# PWM_LED.net
KiCad netlist of a schematic drawn in Altium Designer
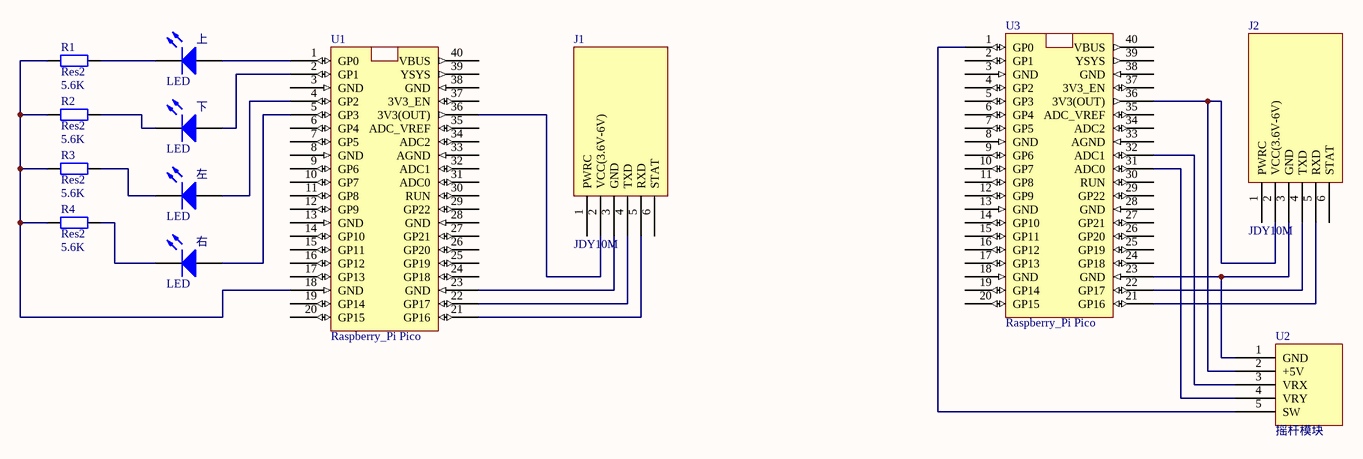
[diagram p0: PWM控制LED.SchDoc]

(export (version "E")
  (design (tool "Eeschema 10.0.6"))
  (components
    (comp (ref "J1") (value "JDY10M") (libsource (lib "元器件") (part "JDY10M")))
    (comp (ref "J2") (value "JDY10M") (libsource (lib "元器件") (part "JDY10M")))
    (comp (ref "R1")
      (value "Res2")
      (footprint "AXIAL-0.4")
      (description "Resistor")
      (fields (field (name "ALTIUM_VALUE") "5.6K") (field (name "PUBLISHER") "Altium Limited"))
      (libsource (lib "Miscellaneous Devices") (part "Res2"))
    )
    (comp (ref "R2")
      (value "Res2")
      (footprint "AXIAL-0.4")
      (description "Resistor")
      (fields (field (name "ALTIUM_VALUE") "5.6K") (field (name "PUBLISHER") "Altium Limited"))
      (libsource (lib "Miscellaneous Devices") (part "Res2"))
    )
    (comp (ref "R3")
      (value "Res2")
      (footprint "AXIAL-0.4")
      (description "Resistor")
      (fields (field (name "ALTIUM_VALUE") "5.6K") (field (name "PUBLISHER") "Altium Limited"))
      (libsource (lib "Miscellaneous Devices") (part "Res2"))
    )
    (comp (ref "R4")
      (value "Res2")
      (footprint "AXIAL-0.4")
      (description "Resistor")
      (fields (field (name "ALTIUM_VALUE") "5.6K") (field (name "PUBLISHER") "Altium Limited"))
      (libsource (lib "Miscellaneous Devices") (part "Res2"))
    )
    (comp (ref "U1") (value "Raspberry_Pi Pico") (libsource (lib "元器件") (part "Raspberry_Pi Pico")))
    (comp (ref "U2") (value "摇杆模块") (libsource (lib "元器件") (part "摇杆模块")))
    (comp (ref "U3") (value "Raspberry_Pi Pico") (libsource (lib "元器件") (part "Raspberry_Pi Pico")))
    (comp (ref "上")
      (value "LED")
      (footprint "LED-0")
      (description "Typical INFRARED GaAs LED")
      (fields (field (name "PUBLISHER") "Altium Limited"))
      (libsource (lib "Miscellaneous Devices") (part "LED0"))
    )
    (comp (ref "下")
      (value "LED")
      (footprint "LED-0")
      (description "Typical INFRARED GaAs LED")
      (fields (field (name "PUBLISHER") "Altium Limited"))
      (libsource (lib "Miscellaneous Devices") (part "LED0"))
    )
    (comp (ref "右")
      (value "LED")
      (footprint "LED-0")
      (description "Typical INFRARED GaAs LED")
      (fields (field (name "PUBLISHER") "Altium Limited"))
      (libsource (lib "Miscellaneous Devices") (part "LED0"))
    )
    (comp (ref "左")
      (value "LED")
      (footprint "LED-0")
      (description "Typical INFRARED GaAs LED")
      (fields (field (name "PUBLISHER") "Altium Limited"))
      (libsource (lib "Miscellaneous Devices") (part "LED0"))
    )
  )
  (nets
    (net (code "1") (name "Net-(J1-GND)") (class "Default")
      (node (ref "J1") (pin "3") (pinfunction "GND_3") (pintype "passive"))
      (node (ref "U1") (pin "23") (pinfunction "GND_23") (pintype "input"))
    )
    (net (code "2") (name "Net-(J1-RXD)") (class "Default")
      (node (ref "J1") (pin "5") (pinfunction "RXD_5") (pintype "passive"))
      (node (ref "U1") (pin "21") (pinfunction "GP16_21") (pintype "bidirectional"))
    )
    (net (code "3") (name "Net-(J1-TXD)") (class "Default")
      (node (ref "J1") (pin "4") (pinfunction "TXD_4") (pintype "passive"))
      (node (ref "U1") (pin "22") (pinfunction "GP17_22") (pintype "bidirectional"))
    )
    (net (code "4") (name "Net-(J1-VCC(3.6V-6V))") (class "Default")
      (node (ref "J1") (pin "2") (pinfunction "VCC(3.6V-6V)_2") (pintype "passive"))
      (node (ref "U1") (pin "36") (pinfunction "3V3(OUT)_36") (pintype "output"))
    )
    (net (code "5") (name "Net-(J2-GND)") (class "Default")
      (node (ref "J2") (pin "3") (pinfunction "GND_3") (pintype "passive"))
      (node (ref "U2") (pin "1") (pinfunction "GND_1") (pintype "passive"))
      (node (ref "U3") (pin "23") (pinfunction "GND_23") (pintype "input"))
    )
    (net (code "6") (name "Net-(J2-RXD)") (class "Default")
      (node (ref "J2") (pin "5") (pinfunction "RXD_5") (pintype "passive"))
      (node (ref "U3") (pin "21") (pinfunction "GP16_21") (pintype "bidirectional"))
    )
    (net (code "7") (name "Net-(J2-TXD)") (class "Default")
      (node (ref "J2") (pin "4") (pinfunction "TXD_4") (pintype "passive"))
      (node (ref "U3") (pin "22") (pinfunction "GP17_22") (pintype "bidirectional"))
    )
    (net (code "8") (name "Net-(J2-VCC(3.6V-6V))") (class "Default")
      (node (ref "J2") (pin "2") (pinfunction "VCC(3.6V-6V)_2") (pintype "passive"))
      (node (ref "U2") (pin "2") (pinfunction "+5V_2") (pintype "passive"))
      (node (ref "U3") (pin "36") (pinfunction "3V3(OUT)_36") (pintype "output"))
    )
    (net (code "9") (name "Net-(R1-Pad1)") (class "Default")
      (node (ref "R1") (pin "1") (pinfunction "1_1") (pintype "passive"))
      (node (ref "R2") (pin "1") (pinfunction "1_1") (pintype "passive"))
      (node (ref "R3") (pin "1") (pinfunction "1_1") (pintype "passive"))
      (node (ref "R4") (pin "1") (pinfunction "1_1") (pintype "passive"))
      (node (ref "U1") (pin "18") (pinfunction "GND_18") (pintype "input"))
    )
    (net (code "10") (name "Net-(U1-GP0)") (class "Default")
      (node (ref "U1") (pin "1") (pinfunction "GP0_1") (pintype "bidirectional"))
      (node (ref "上") (pin "1") (pinfunction "A_1") (pintype "passive"))
    )
    (net (code "11") (name "Net-(U1-GP1)") (class "Default")
      (node (ref "U1") (pin "2") (pinfunction "GP1_2") (pintype "bidirectional"))
      (node (ref "下") (pin "1") (pinfunction "A_1") (pintype "passive"))
    )
    (net (code "12") (name "Net-(U1-GP2)") (class "Default")
      (node (ref "U1") (pin "4") (pinfunction "GP2_4") (pintype "bidirectional"))
      (node (ref "左") (pin "1") (pinfunction "A_1") (pintype "passive"))
    )
    (net (code "13") (name "Net-(U1-GP3)") (class "Default")
      (node (ref "U1") (pin "5") (pinfunction "GP3_5") (pintype "bidirectional"))
      (node (ref "右") (pin "1") (pinfunction "A_1") (pintype "passive"))
    )
    (net (code "14") (name "Net-(U2-SW)") (class "Default")
      (node (ref "U2") (pin "5") (pinfunction "SW_5") (pintype "passive"))
      (node (ref "U3") (pin "1") (pinfunction "GP0_1") (pintype "bidirectional"))
    )
    (net (code "15") (name "Net-(U2-VRX)") (class "Default")
      (node (ref "U2") (pin "3") (pinfunction "VRX_3") (pintype "passive"))
      (node (ref "U3") (pin "32") (pinfunction "ADC1_32") (pintype "bidirectional"))
    )
    (net (code "16") (name "Net-(U2-VRY)") (class "Default")
      (node (ref "U2") (pin "4") (pinfunction "VRY_4") (pintype "passive"))
      (node (ref "U3") (pin "31") (pinfunction "ADC0_31") (pintype "bidirectional"))
    )
    (net (code "17") (name "Net-(上-K)") (class "Default")
      (node (ref "R1") (pin "2") (pinfunction "2_2") (pintype "passive"))
      (node (ref "上") (pin "2") (pinfunction "K_2") (pintype "passive"))
    )
    (net (code "18") (name "Net-(下-K)") (class "Default")
      (node (ref "R2") (pin "2") (pinfunction "2_2") (pintype "passive"))
      (node (ref "下") (pin "2") (pinfunction "K_2") (pintype "passive"))
    )
    (net (code "19") (name "Net-(右-K)") (class "Default")
      (node (ref "R4") (pin "2") (pinfunction "2_2") (pintype "passive"))
      (node (ref "右") (pin "2") (pinfunction "K_2") (pintype "passive"))
    )
    (net (code "20") (name "Net-(左-K)") (class "Default")
      (node (ref "R3") (pin "2") (pinfunction "2_2") (pintype "passive"))
      (node (ref "左") (pin "2") (pinfunction "K_2") (pintype "passive"))
    )
    (net (code "21") (name "unconnected-(J1-PWRC-Pad1)") (class "Default")
      (node (ref "J1") (pin "1") (pinfunction "PWRC_1") (pintype "passive"))
    )
    (net (code "22") (name "unconnected-(J1-STAT-Pad6)") (class "Default")
      (node (ref "J1") (pin "6") (pinfunction "STAT_6") (pintype "passive"))
    )
    (net (code "23") (name "unconnected-(J2-PWRC-Pad1)") (class "Default")
      (node (ref "J2") (pin "1") (pinfunction "PWRC_1") (pintype "passive"))
    )
    (net (code "24") (name "unconnected-(J2-STAT-Pad6)") (class "Default")
      (node (ref "J2") (pin "6") (pinfunction "STAT_6") (pintype "passive"))
    )
    (net (code "25") (name "unconnected-(U1-3V3_EN-Pad37)") (class "Default")
      (node (ref "U1") (pin "37") (pinfunction "3V3_EN_37") (pintype "bidirectional"))
    )
    (net (code "26") (name "unconnected-(U1-ADC0-Pad31)") (class "Default")
      (node (ref "U1") (pin "31") (pinfunction "ADC0_31") (pintype "bidirectional"))
    )
    (net (code "27") (name "unconnected-(U1-ADC1-Pad32)") (class "Default")
      (node (ref "U1") (pin "32") (pinfunction "ADC1_32") (pintype "bidirectional"))
    )
    (net (code "28") (name "unconnected-(U1-ADC2-Pad34)") (class "Default")
      (node (ref "U1") (pin "34") (pinfunction "ADC2_34") (pintype "bidirectional"))
    )
    (net (code "29") (name "unconnected-(U1-ADC_VREF-Pad35)") (class "Default")
      (node (ref "U1") (pin "35") (pinfunction "ADC_VREF_35") (pintype "bidirectional"))
    )
    (net (code "30") (name "unconnected-(U1-AGND-Pad33)") (class "Default")
      (node (ref "U1") (pin "33") (pinfunction "AGND_33") (pintype "input"))
    )
    (net (code "31") (name "unconnected-(U1-GND-Pad3)") (class "Default")
      (node (ref "U1") (pin "3") (pinfunction "GND_3") (pintype "input"))
    )
    (net (code "32") (name "unconnected-(U1-GND-Pad8)") (class "Default")
      (node (ref "U1") (pin "8") (pinfunction "GND_8") (pintype "input"))
    )
    (net (code "33") (name "unconnected-(U1-GND-Pad13)") (class "Default")
      (node (ref "U1") (pin "13") (pinfunction "GND_13") (pintype "input"))
    )
    (net (code "34") (name "unconnected-(U1-GND-Pad28)") (class "Default")
      (node (ref "U1") (pin "28") (pinfunction "GND_28") (pintype "input"))
    )
    (net (code "35") (name "unconnected-(U1-GND-Pad38)") (class "Default")
      (node (ref "U1") (pin "38") (pinfunction "GND_38") (pintype "input"))
    )
    (net (code "36") (name "unconnected-(U1-GP4-Pad6)") (class "Default")
      (node (ref "U1") (pin "6") (pinfunction "GP4_6") (pintype "bidirectional"))
    )
    (net (code "37") (name "unconnected-(U1-GP5-Pad7)") (class "Default")
      (node (ref "U1") (pin "7") (pinfunction "GP5_7") (pintype "bidirectional"))
    )
    (net (code "38") (name "unconnected-(U1-GP6-Pad9)") (class "Default")
      (node (ref "U1") (pin "9") (pinfunction "GP6_9") (pintype "bidirectional"))
    )
    (net (code "39") (name "unconnected-(U1-GP7-Pad10)") (class "Default")
      (node (ref "U1") (pin "10") (pinfunction "GP7_10") (pintype "bidirectional"))
    )
    (net (code "40") (name "unconnected-(U1-GP8-Pad11)") (class "Default")
      (node (ref "U1") (pin "11") (pinfunction "GP8_11") (pintype "bidirectional"))
    )
    (net (code "41") (name "unconnected-(U1-GP9-Pad12)") (class "Default")
      (node (ref "U1") (pin "12") (pinfunction "GP9_12") (pintype "bidirectional"))
    )
    (net (code "42") (name "unconnected-(U1-GP10-Pad14)") (class "Default")
      (node (ref "U1") (pin "14") (pinfunction "GP10_14") (pintype "bidirectional"))
    )
    (net (code "43") (name "unconnected-(U1-GP11-Pad15)") (class "Default")
      (node (ref "U1") (pin "15") (pinfunction "GP11_15") (pintype "bidirectional"))
    )
    (net (code "44") (name "unconnected-(U1-GP12-Pad16)") (class "Default")
      (node (ref "U1") (pin "16") (pinfunction "GP12_16") (pintype "bidirectional"))
    )
    (net (code "45") (name "unconnected-(U1-GP13-Pad17)") (class "Default")
      (node (ref "U1") (pin "17") (pinfunction "GP13_17") (pintype "bidirectional"))
    )
    (net (code "46") (name "unconnected-(U1-GP14-Pad19)") (class "Default")
      (node (ref "U1") (pin "19") (pinfunction "GP14_19") (pintype "bidirectional"))
    )
    (net (code "47") (name "unconnected-(U1-GP15-Pad20)") (class "Default")
      (node (ref "U1") (pin "20") (pinfunction "GP15_20") (pintype "bidirectional"))
    )
    (net (code "48") (name "unconnected-(U1-GP18-Pad24)") (class "Default")
      (node (ref "U1") (pin "24") (pinfunction "GP18_24") (pintype "bidirectional"))
    )
    (net (code "49") (name "unconnected-(U1-GP19-Pad25)") (class "Default")
      (node (ref "U1") (pin "25") (pinfunction "GP19_25") (pintype "bidirectional"))
    )
    (net (code "50") (name "unconnected-(U1-GP20-Pad26)") (class "Default")
      (node (ref "U1") (pin "26") (pinfunction "GP20_26") (pintype "bidirectional"))
    )
    (net (code "51") (name "unconnected-(U1-GP21-Pad27)") (class "Default")
      (node (ref "U1") (pin "27") (pinfunction "GP21_27") (pintype "bidirectional"))
    )
    (net (code "52") (name "unconnected-(U1-GP22-Pad29)") (class "Default")
      (node (ref "U1") (pin "29") (pinfunction "GP22_29") (pintype "bidirectional"))
    )
    (net (code "53") (name "unconnected-(U1-RUN-Pad30)") (class "Default")
      (node (ref "U1") (pin "30") (pinfunction "RUN_30") (pintype "bidirectional"))
    )
    (net (code "54") (name "unconnected-(U1-VBUS-Pad40)") (class "Default")
      (node (ref "U1") (pin "40") (pinfunction "VBUS_40") (pintype "output"))
    )
    (net (code "55") (name "unconnected-(U1-YSYS-Pad39)") (class "Default")
      (node (ref "U1") (pin "39") (pinfunction "YSYS_39") (pintype "output"))
    )
    (net (code "56") (name "unconnected-(U3-3V3_EN-Pad37)") (class "Default")
      (node (ref "U3") (pin "37") (pinfunction "3V3_EN_37") (pintype "bidirectional"))
    )
    (net (code "57") (name "unconnected-(U3-ADC2-Pad34)") (class "Default")
      (node (ref "U3") (pin "34") (pinfunction "ADC2_34") (pintype "bidirectional"))
    )
    (net (code "58") (name "unconnected-(U3-ADC_VREF-Pad35)") (class "Default")
      (node (ref "U3") (pin "35") (pinfunction "ADC_VREF_35") (pintype "bidirectional"))
    )
    (net (code "59") (name "unconnected-(U3-AGND-Pad33)") (class "Default")
      (node (ref "U3") (pin "33") (pinfunction "AGND_33") (pintype "input"))
    )
    (net (code "60") (name "unconnected-(U3-GND-Pad3)") (class "Default")
      (node (ref "U3") (pin "3") (pinfunction "GND_3") (pintype "input"))
    )
    (net (code "61") (name "unconnected-(U3-GND-Pad8)") (class "Default")
      (node (ref "U3") (pin "8") (pinfunction "GND_8") (pintype "input"))
    )
    (net (code "62") (name "unconnected-(U3-GND-Pad13)") (class "Default")
      (node (ref "U3") (pin "13") (pinfunction "GND_13") (pintype "input"))
    )
    (net (code "63") (name "unconnected-(U3-GND-Pad18)") (class "Default")
      (node (ref "U3") (pin "18") (pinfunction "GND_18") (pintype "input"))
    )
    (net (code "64") (name "unconnected-(U3-GND-Pad28)") (class "Default")
      (node (ref "U3") (pin "28") (pinfunction "GND_28") (pintype "input"))
    )
    (net (code "65") (name "unconnected-(U3-GND-Pad38)") (class "Default")
      (node (ref "U3") (pin "38") (pinfunction "GND_38") (pintype "input"))
    )
    (net (code "66") (name "unconnected-(U3-GP1-Pad2)") (class "Default")
      (node (ref "U3") (pin "2") (pinfunction "GP1_2") (pintype "bidirectional"))
    )
    (net (code "67") (name "unconnected-(U3-GP2-Pad4)") (class "Default")
      (node (ref "U3") (pin "4") (pinfunction "GP2_4") (pintype "bidirectional"))
    )
    (net (code "68") (name "unconnected-(U3-GP3-Pad5)") (class "Default")
      (node (ref "U3") (pin "5") (pinfunction "GP3_5") (pintype "bidirectional"))
    )
    (net (code "69") (name "unconnected-(U3-GP4-Pad6)") (class "Default")
      (node (ref "U3") (pin "6") (pinfunction "GP4_6") (pintype "bidirectional"))
    )
    (net (code "70") (name "unconnected-(U3-GP5-Pad7)") (class "Default")
      (node (ref "U3") (pin "7") (pinfunction "GP5_7") (pintype "bidirectional"))
    )
    (net (code "71") (name "unconnected-(U3-GP6-Pad9)") (class "Default")
      (node (ref "U3") (pin "9") (pinfunction "GP6_9") (pintype "bidirectional"))
    )
    (net (code "72") (name "unconnected-(U3-GP7-Pad10)") (class "Default")
      (node (ref "U3") (pin "10") (pinfunction "GP7_10") (pintype "bidirectional"))
    )
    (net (code "73") (name "unconnected-(U3-GP8-Pad11)") (class "Default")
      (node (ref "U3") (pin "11") (pinfunction "GP8_11") (pintype "bidirectional"))
    )
    (net (code "74") (name "unconnected-(U3-GP9-Pad12)") (class "Default")
      (node (ref "U3") (pin "12") (pinfunction "GP9_12") (pintype "bidirectional"))
    )
    (net (code "75") (name "unconnected-(U3-GP10-Pad14)") (class "Default")
      (node (ref "U3") (pin "14") (pinfunction "GP10_14") (pintype "bidirectional"))
    )
    (net (code "76") (name "unconnected-(U3-GP11-Pad15)") (class "Default")
      (node (ref "U3") (pin "15") (pinfunction "GP11_15") (pintype "bidirectional"))
    )
    (net (code "77") (name "unconnected-(U3-GP12-Pad16)") (class "Default")
      (node (ref "U3") (pin "16") (pinfunction "GP12_16") (pintype "bidirectional"))
    )
    (net (code "78") (name "unconnected-(U3-GP13-Pad17)") (class "Default")
      (node (ref "U3") (pin "17") (pinfunction "GP13_17") (pintype "bidirectional"))
    )
    (net (code "79") (name "unconnected-(U3-GP14-Pad19)") (class "Default")
      (node (ref "U3") (pin "19") (pinfunction "GP14_19") (pintype "bidirectional"))
    )
    (net (code "80") (name "unconnected-(U3-GP15-Pad20)") (class "Default")
      (node (ref "U3") (pin "20") (pinfunction "GP15_20") (pintype "bidirectional"))
    )
    (net (code "81") (name "unconnected-(U3-GP18-Pad24)") (class "Default")
      (node (ref "U3") (pin "24") (pinfunction "GP18_24") (pintype "bidirectional"))
    )
    (net (code "82") (name "unconnected-(U3-GP19-Pad25)") (class "Default")
      (node (ref "U3") (pin "25") (pinfunction "GP19_25") (pintype "bidirectional"))
    )
    (net (code "83") (name "unconnected-(U3-GP20-Pad26)") (class "Default")
      (node (ref "U3") (pin "26") (pinfunction "GP20_26") (pintype "bidirectional"))
    )
    (net (code "84") (name "unconnected-(U3-GP21-Pad27)") (class "Default")
      (node (ref "U3") (pin "27") (pinfunction "GP21_27") (pintype "bidirectional"))
    )
    (net (code "85") (name "unconnected-(U3-GP22-Pad29)") (class "Default")
      (node (ref "U3") (pin "29") (pinfunction "GP22_29") (pintype "bidirectional"))
    )
    (net (code "86") (name "unconnected-(U3-RUN-Pad30)") (class "Default")
      (node (ref "U3") (pin "30") (pinfunction "RUN_30") (pintype "bidirectional"))
    )
    (net (code "87") (name "unconnected-(U3-VBUS-Pad40)") (class "Default")
      (node (ref "U3") (pin "40") (pinfunction "VBUS_40") (pintype "output"))
    )
    (net (code "88") (name "unconnected-(U3-YSYS-Pad39)") (class "Default")
      (node (ref "U3") (pin "39") (pinfunction "YSYS_39") (pintype "output"))
    )
  )
)
